# senseinterface.net
KiCad netlist of a schematic drawn in Altium Designer
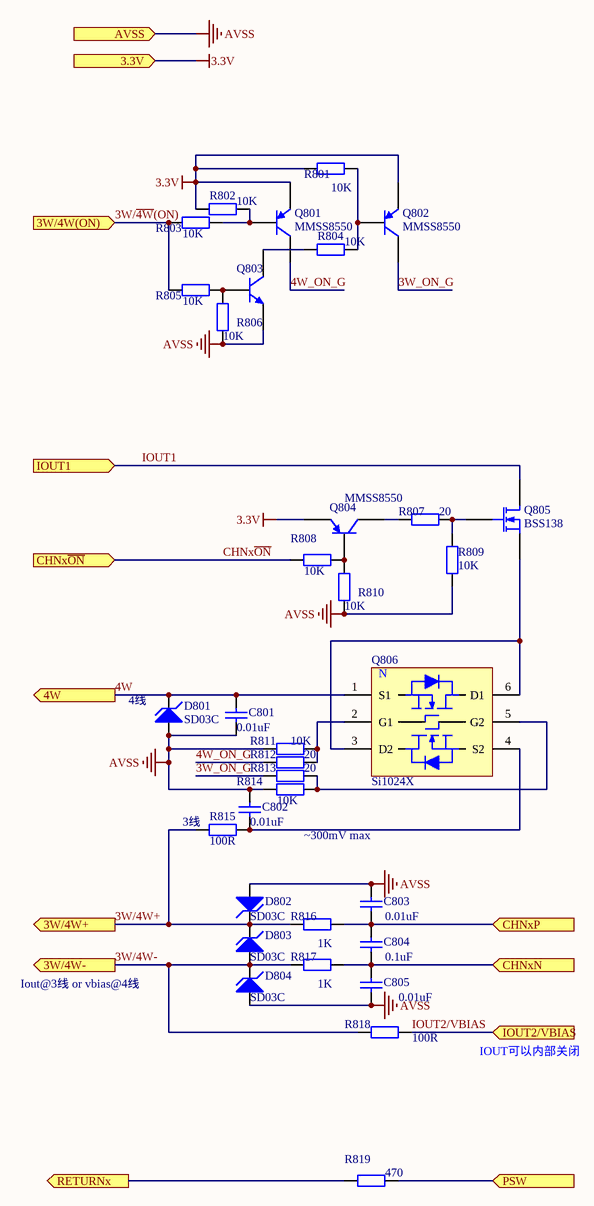
[diagram p0: senseinterface.SchDoc]

(export (version "E")
  (design (tool "Eeschema 10.0.6"))
  (components
    (comp (ref "C801")
      (value "0.01uF")
      (footprint "0805c")
      (description "Capacitor")
      (fields (field (name "Comment") "CC0805MRX7R9BB103") (field (name "PUBLISHER") "Altium Limited"))
      (libsource (lib "Miscellaneous Devices") (part "Cap"))
    )
    (comp (ref "C802")
      (value "0.01uF")
      (footprint "0805c")
      (description "Capacitor")
      (fields (field (name "Comment") "CC0805MRX7R9BB103") (field (name "PUBLISHER") "Altium Limited"))
      (libsource (lib "Miscellaneous Devices") (part "Cap"))
    )
    (comp (ref "C803")
      (value "0.01uF")
      (footprint "0805c")
      (description "Capacitor")
      (fields (field (name "Comment") "CC0805MRX7R9BB103") (field (name "PUBLISHER") "Altium Limited"))
      (libsource (lib "Miscellaneous Devices") (part "Cap"))
    )
    (comp (ref "C804")
      (value "0.1uF")
      (footprint "0805c")
      (description "Capacitor")
      (fields (field (name "Comment") "CC0805MRX7R9BB104") (field (name "PUBLISHER") "Altium Limited"))
      (libsource (lib "Miscellaneous Devices") (part "Cap"))
    )
    (comp (ref "C805")
      (value "0.01uF")
      (footprint "0805c")
      (description "Capacitor")
      (fields (field (name "Comment") "CC0805MRX7R9BB103") (field (name "PUBLISHER") "Altium Limited"))
      (libsource (lib "Miscellaneous Devices") (part "Cap"))
    )
    (comp (ref "D801")
      (value "SD03C")
      (footprint "sod323")
      (libsource (lib "Standard-V0.0") (part "TVS DIODE"))
    )
    (comp (ref "D802")
      (value "SD03C")
      (footprint "sod323")
      (libsource (lib "Standard-V0.0") (part "TVS DIODE"))
    )
    (comp (ref "D803")
      (value "SD03C")
      (footprint "sod323")
      (libsource (lib "Standard-V0.0") (part "TVS DIODE"))
    )
    (comp (ref "D804")
      (value "SD03C")
      (footprint "sod323")
      (libsource (lib "Standard-V0.0") (part "TVS DIODE"))
    )
    (comp (ref "Q801")
      (value "MMSS8550")
      (footprint "SOT-23-BJT")
      (description "PNP Bipolar Transistor")
      (fields (field (name "PUBLISHER") "Altium Limited"))
      (libsource (lib "Miscellaneous Devices") (part "PNP"))
    )
    (comp (ref "Q802")
      (value "MMSS8550")
      (footprint "SOT-23-BJT")
      (description "PNP Bipolar Transistor")
      (fields (field (name "PUBLISHER") "Altium Limited"))
      (libsource (lib "Miscellaneous Devices") (part "PNP"))
    )
    (comp (ref "Q803")
      (value "MMSS8050")
      (footprint "SOT-23-BJT")
      (description "NPN Bipolar Transistor")
      (fields (field (name "PUBLISHER") "Altium Limited"))
      (libsource (lib "Miscellaneous Devices") (part "NPN"))
    )
    (comp (ref "Q804")
      (value "MMSS8550")
      (footprint "SOT-23-BJT")
      (description "PNP Bipolar Transistor")
      (fields (field (name "PUBLISHER") "Altium Limited"))
      (libsource (lib "Miscellaneous Devices") (part "PNP"))
    )
    (comp (ref "Q805")
      (value "BSS138")
      (footprint "E3")
      (description "N-Channel MOSFET")
      (fields (field (name "PUBLISHER") "Altium Limited"))
      (libsource (lib "Miscellaneous Devices") (part "MOSFET-N"))
    )
    (comp (ref "Q806")
      (value "Si1024X")
      (footprint "SOT563F(SC-89-6)")
      (libsource (lib "Standard-V0.0") (part "Si1024X"))
    )
    (comp (ref "R801")
      (value "10K")
      (footprint "0805R")
      (description "Resistor")
      (fields (field (name "Comment") "RC0805JR-0710KL") (field (name "PUBLISHER") "Altium Limited"))
      (libsource (lib "Miscellaneous Devices") (part "Res2"))
    )
    (comp (ref "R802")
      (value "10K")
      (footprint "0805R")
      (description "Resistor")
      (fields (field (name "Comment") "RC0805JR-0710KL") (field (name "PUBLISHER") "Altium Limited"))
      (libsource (lib "Miscellaneous Devices") (part "Res2"))
    )
    (comp (ref "R803")
      (value "10K")
      (footprint "0805R")
      (description "Resistor")
      (fields (field (name "Comment") "RC0805JR-0710KL") (field (name "PUBLISHER") "Altium Limited"))
      (libsource (lib "Miscellaneous Devices") (part "Res2"))
    )
    (comp (ref "R804")
      (value "10K")
      (footprint "0805R")
      (description "Resistor")
      (fields (field (name "Comment") "RC0805JR-0710KL") (field (name "PUBLISHER") "Altium Limited"))
      (libsource (lib "Miscellaneous Devices") (part "Res2"))
    )
    (comp (ref "R805")
      (value "10K")
      (footprint "0805R")
      (description "Resistor")
      (fields (field (name "Comment") "RC0805JR-0710KL") (field (name "PUBLISHER") "Altium Limited"))
      (libsource (lib "Miscellaneous Devices") (part "Res2"))
    )
    (comp (ref "R806")
      (value "10K")
      (footprint "0805R")
      (description "Resistor")
      (fields (field (name "Comment") "RC0805JR-0710KL") (field (name "PUBLISHER") "Altium Limited"))
      (libsource (lib "") (part "Res2_2"))
    )
    (comp (ref "R807")
      (value "20")
      (footprint "0805R")
      (description "Resistor")
      (fields (field (name "Comment") "RC0805JR-0720RL") (field (name "PUBLISHER") "Altium Limited"))
      (libsource (lib "") (part "Res2_1"))
    )
    (comp (ref "R808")
      (value "10K")
      (footprint "0805R")
      (description "Resistor")
      (fields (field (name "Comment") "RC0805JR-0710KL") (field (name "PUBLISHER") "Altium Limited"))
      (libsource (lib "Miscellaneous Devices") (part "Res2"))
    )
    (comp (ref "R809")
      (value "10K")
      (footprint "0805R")
      (description "Resistor")
      (fields (field (name "Comment") "RC0805JR-0710KL") (field (name "PUBLISHER") "Altium Limited"))
      (libsource (lib "") (part "Res2_2"))
    )
    (comp (ref "R810")
      (value "10K")
      (footprint "0805R")
      (description "Resistor")
      (fields (field (name "Comment") "RC0805JR-0710KL") (field (name "PUBLISHER") "Altium Limited"))
      (libsource (lib "") (part "Res2_2"))
    )
    (comp (ref "R811")
      (value "10K")
      (footprint "0805R")
      (description "Resistor")
      (fields (field (name "Comment") "RC0805JR-0710KL") (field (name "PUBLISHER") "Altium Limited"))
      (libsource (lib "") (part "Res2_1"))
    )
    (comp (ref "R812")
      (value "20")
      (footprint "0805R")
      (description "Resistor")
      (fields (field (name "Comment") "RC0805JR-0720RL") (field (name "PUBLISHER") "Altium Limited"))
      (libsource (lib "") (part "Res2_1"))
    )
    (comp (ref "R813")
      (value "20")
      (footprint "0805R")
      (description "Resistor")
      (fields (field (name "Comment") "RC0805JR-0720RL") (field (name "PUBLISHER") "Altium Limited"))
      (libsource (lib "") (part "Res2_1"))
    )
    (comp (ref "R814")
      (value "10K")
      (footprint "0805R")
      (description "Resistor")
      (fields (field (name "Comment") "RC0805JR-0710KL") (field (name "PUBLISHER") "Altium Limited"))
      (libsource (lib "") (part "Res2_1"))
    )
    (comp (ref "R815")
      (value "100R")
      (footprint "0805R")
      (description "Resistor")
      (fields (field (name "Comment") "RC0805JR-07100RL") (field (name "PUBLISHER") "Altium Limited"))
      (libsource (lib "") (part "Res2_1"))
    )
    (comp (ref "R816")
      (value "1K")
      (footprint "0805R")
      (description "Resistor")
      (fields (field (name "Comment") "RC0805JR-071KL") (field (name "PUBLISHER") "Altium Limited"))
      (libsource (lib "Miscellaneous Devices") (part "Res2"))
    )
    (comp (ref "R817")
      (value "1K")
      (footprint "0805R")
      (description "Resistor")
      (fields (field (name "Comment") "RC0805JR-071KL") (field (name "PUBLISHER") "Altium Limited"))
      (libsource (lib "Miscellaneous Devices") (part "Res2"))
    )
    (comp (ref "R818")
      (value "100R")
      (footprint "0805R")
      (description "Resistor")
      (fields (field (name "Comment") "RC0805JR-07100RL") (field (name "PUBLISHER") "Altium Limited"))
      (libsource (lib "Miscellaneous Devices") (part "Res2"))
    )
    (comp (ref "R819")
      (value "470")
      (footprint "0805R")
      (description "Resistor")
      (fields (field (name "Comment") "RC0805JR-07470RL") (field (name "PUBLISHER") "Altium Limited"))
      (libsource (lib "Miscellaneous Devices") (part "Res2"))
    )
  )
  (nets
    (net (code "1") (name "/3W_ON_G") (class "Default")
      (node (ref "Q802") (pin "1") (pinfunction "C_1") (pintype "passive"))
      (node (ref "R813") (pin "1") (pinfunction "1_1") (pintype "passive"))
    )
    (net (code "2") (name "/3W{slash}4W+") (class "Default")
      (node (ref "D802") (pin "2") (pinfunction "CATHODE_2") (pintype "passive"))
      (node (ref "D803") (pin "2") (pinfunction "CATHODE_2") (pintype "passive"))
      (node (ref "R815") (pin "1") (pinfunction "1_1") (pintype "passive"))
      (node (ref "R816") (pin "2") (pinfunction "2_2") (pintype "passive"))
    )
    (net (code "3") (name "/3W{slash}4W-") (class "Default")
      (node (ref "D803") (pin "1") (pinfunction "ANODE_1") (pintype "passive"))
      (node (ref "D804") (pin "2") (pinfunction "CATHODE_2") (pintype "passive"))
      (node (ref "R817") (pin "2") (pinfunction "2_2") (pintype "passive"))
      (node (ref "R818") (pin "2") (pinfunction "2_2") (pintype "passive"))
    )
    (net (code "4") (name "/3W{slash}~{4W}(ON)") (class "Default")
      (node (ref "R803") (pin "2") (pinfunction "2_2") (pintype "passive"))
      (node (ref "R805") (pin "2") (pinfunction "2_2") (pintype "passive"))
    )
    (net (code "5") (name "/4W") (class "Default")
      (node (ref "C801") (pin "1") (pinfunction "1_1") (pintype "passive"))
      (node (ref "D801") (pin "2") (pinfunction "CATHODE_2") (pintype "passive"))
      (node (ref "Q806") (pin "1") (pinfunction "S1_1") (pintype "passive"))
    )
    (net (code "6") (name "/4W_ON_G") (class "Default")
      (node (ref "Q801") (pin "1") (pinfunction "C_1") (pintype "passive"))
      (node (ref "R812") (pin "1") (pinfunction "1_1") (pintype "passive"))
    )
    (net (code "7") (name "/CHNxN") (class "Default")
      (node (ref "C804") (pin "2") (pinfunction "2_2") (pintype "passive"))
      (node (ref "C805") (pin "1") (pinfunction "1_1") (pintype "passive"))
      (node (ref "R817") (pin "1") (pinfunction "1_1") (pintype "passive"))
    )
    (net (code "8") (name "/CHNxP") (class "Default")
      (node (ref "C803") (pin "1") (pinfunction "1_1") (pintype "passive"))
      (node (ref "C804") (pin "1") (pinfunction "1_1") (pintype "passive"))
      (node (ref "R816") (pin "1") (pinfunction "1_1") (pintype "passive"))
    )
    (net (code "9") (name "/CHNx~{ON}") (class "Default")
      (node (ref "R808") (pin "2") (pinfunction "2_2") (pintype "passive"))
    )
    (net (code "10") (name "/IOUT1") (class "Default")
      (node (ref "Q805") (pin "1") (pinfunction "D_1") (pintype "passive"))
    )
    (net (code "11") (name "/IOUT2{slash}VBIAS") (class "Default")
      (node (ref "R818") (pin "1") (pinfunction "1_1") (pintype "passive"))
    )
    (net (code "12") (name "/PSW") (class "Default")
      (node (ref "R819") (pin "1") (pinfunction "1_1") (pintype "passive"))
    )
    (net (code "13") (name "/RETURNx") (class "Default")
      (node (ref "R819") (pin "2") (pinfunction "2_2") (pintype "passive"))
    )
    (net (code "14") (name "3.3V") (class "Default")
      (node (ref "Q801") (pin "3") (pinfunction "E_3") (pintype "passive"))
      (node (ref "Q802") (pin "3") (pinfunction "E_3") (pintype "passive"))
      (node (ref "Q804") (pin "3") (pinfunction "E_3") (pintype "passive"))
      (node (ref "R801") (pin "2") (pinfunction "2_2") (pintype "passive"))
      (node (ref "R802") (pin "2") (pinfunction "2_2") (pintype "passive"))
    )
    (net (code "15") (name "AVSS") (class "Default")
      (node (ref "C801") (pin "2") (pinfunction "2_2") (pintype "passive"))
      (node (ref "C802") (pin "1") (pinfunction "1_1") (pintype "passive"))
      (node (ref "C803") (pin "2") (pinfunction "2_2") (pintype "passive"))
      (node (ref "C805") (pin "2") (pinfunction "2_2") (pintype "passive"))
      (node (ref "D801") (pin "1") (pinfunction "ANODE_1") (pintype "passive"))
      (node (ref "D802") (pin "1") (pinfunction "ANODE_1") (pintype "passive"))
      (node (ref "D804") (pin "1") (pinfunction "ANODE_1") (pintype "passive"))
      (node (ref "Q803") (pin "3") (pinfunction "E_3") (pintype "passive"))
      (node (ref "R806") (pin "2") (pinfunction "2_2") (pintype "passive"))
      (node (ref "R809") (pin "2") (pinfunction "2_2") (pintype "passive"))
      (node (ref "R810") (pin "2") (pinfunction "2_2") (pintype "passive"))
      (node (ref "R811") (pin "1") (pinfunction "1_1") (pintype "passive"))
      (node (ref "R814") (pin "1") (pinfunction "1_1") (pintype "passive"))
    )
    (net (code "16") (name "Net-(Q801-B)") (class "Default")
      (node (ref "Q801") (pin "2") (pinfunction "B_2") (pintype "passive"))
      (node (ref "R802") (pin "1") (pinfunction "1_1") (pintype "passive"))
      (node (ref "R803") (pin "1") (pinfunction "1_1") (pintype "passive"))
    )
    (net (code "17") (name "Net-(Q802-B)") (class "Default")
      (node (ref "Q802") (pin "2") (pinfunction "B_2") (pintype "passive"))
      (node (ref "R801") (pin "1") (pinfunction "1_1") (pintype "passive"))
      (node (ref "R804") (pin "1") (pinfunction "1_1") (pintype "passive"))
    )
    (net (code "18") (name "Net-(Q803-B)") (class "Default")
      (node (ref "Q803") (pin "2") (pinfunction "B_2") (pintype "passive"))
      (node (ref "R805") (pin "1") (pinfunction "1_1") (pintype "passive"))
      (node (ref "R806") (pin "1") (pinfunction "1_1") (pintype "passive"))
    )
    (net (code "19") (name "Net-(Q803-C)") (class "Default")
      (node (ref "Q803") (pin "1") (pinfunction "C_1") (pintype "passive"))
      (node (ref "R804") (pin "2") (pinfunction "2_2") (pintype "passive"))
    )
    (net (code "20") (name "Net-(Q804-B)") (class "Default")
      (node (ref "Q804") (pin "2") (pinfunction "B_2") (pintype "passive"))
      (node (ref "R808") (pin "1") (pinfunction "1_1") (pintype "passive"))
      (node (ref "R810") (pin "1") (pinfunction "1_1") (pintype "passive"))
    )
    (net (code "21") (name "Net-(Q804-C)") (class "Default")
      (node (ref "Q804") (pin "1") (pinfunction "C_1") (pintype "passive"))
      (node (ref "R807") (pin "1") (pinfunction "1_1") (pintype "passive"))
    )
    (net (code "22") (name "Net-(Q805-G)") (class "Default")
      (node (ref "Q805") (pin "2") (pinfunction "G_2") (pintype "passive"))
      (node (ref "R807") (pin "2") (pinfunction "2_2") (pintype "passive"))
      (node (ref "R809") (pin "1") (pinfunction "1_1") (pintype "passive"))
    )
    (net (code "23") (name "Net-(Q805-S)") (class "Default")
      (node (ref "Q805") (pin "3") (pinfunction "S_3") (pintype "passive"))
      (node (ref "Q806") (pin "3") (pinfunction "D2_3") (pintype "passive"))
      (node (ref "Q806") (pin "6") (pinfunction "D1_6") (pintype "passive"))
    )
    (net (code "24") (name "Net-(Q806-G1)") (class "Default")
      (node (ref "Q806") (pin "2") (pinfunction "G1_2") (pintype "passive"))
      (node (ref "R811") (pin "2") (pinfunction "2_2") (pintype "passive"))
      (node (ref "R812") (pin "2") (pinfunction "2_2") (pintype "passive"))
    )
    (net (code "25") (name "Net-(Q806-G2)") (class "Default")
      (node (ref "Q806") (pin "5") (pinfunction "G2_5") (pintype "passive"))
      (node (ref "R813") (pin "2") (pinfunction "2_2") (pintype "passive"))
      (node (ref "R814") (pin "2") (pinfunction "2_2") (pintype "passive"))
    )
    (net (code "26") (name "Net-(Q806-S2)") (class "Default")
      (node (ref "C802") (pin "2") (pinfunction "2_2") (pintype "passive"))
      (node (ref "Q806") (pin "4") (pinfunction "S2_4") (pintype "passive"))
      (node (ref "R815") (pin "2") (pinfunction "2_2") (pintype "passive"))
    )
  )
)
